# YarnControl_Driver_v1_1.net
KiCad netlist of a schematic drawn in Altium Designer
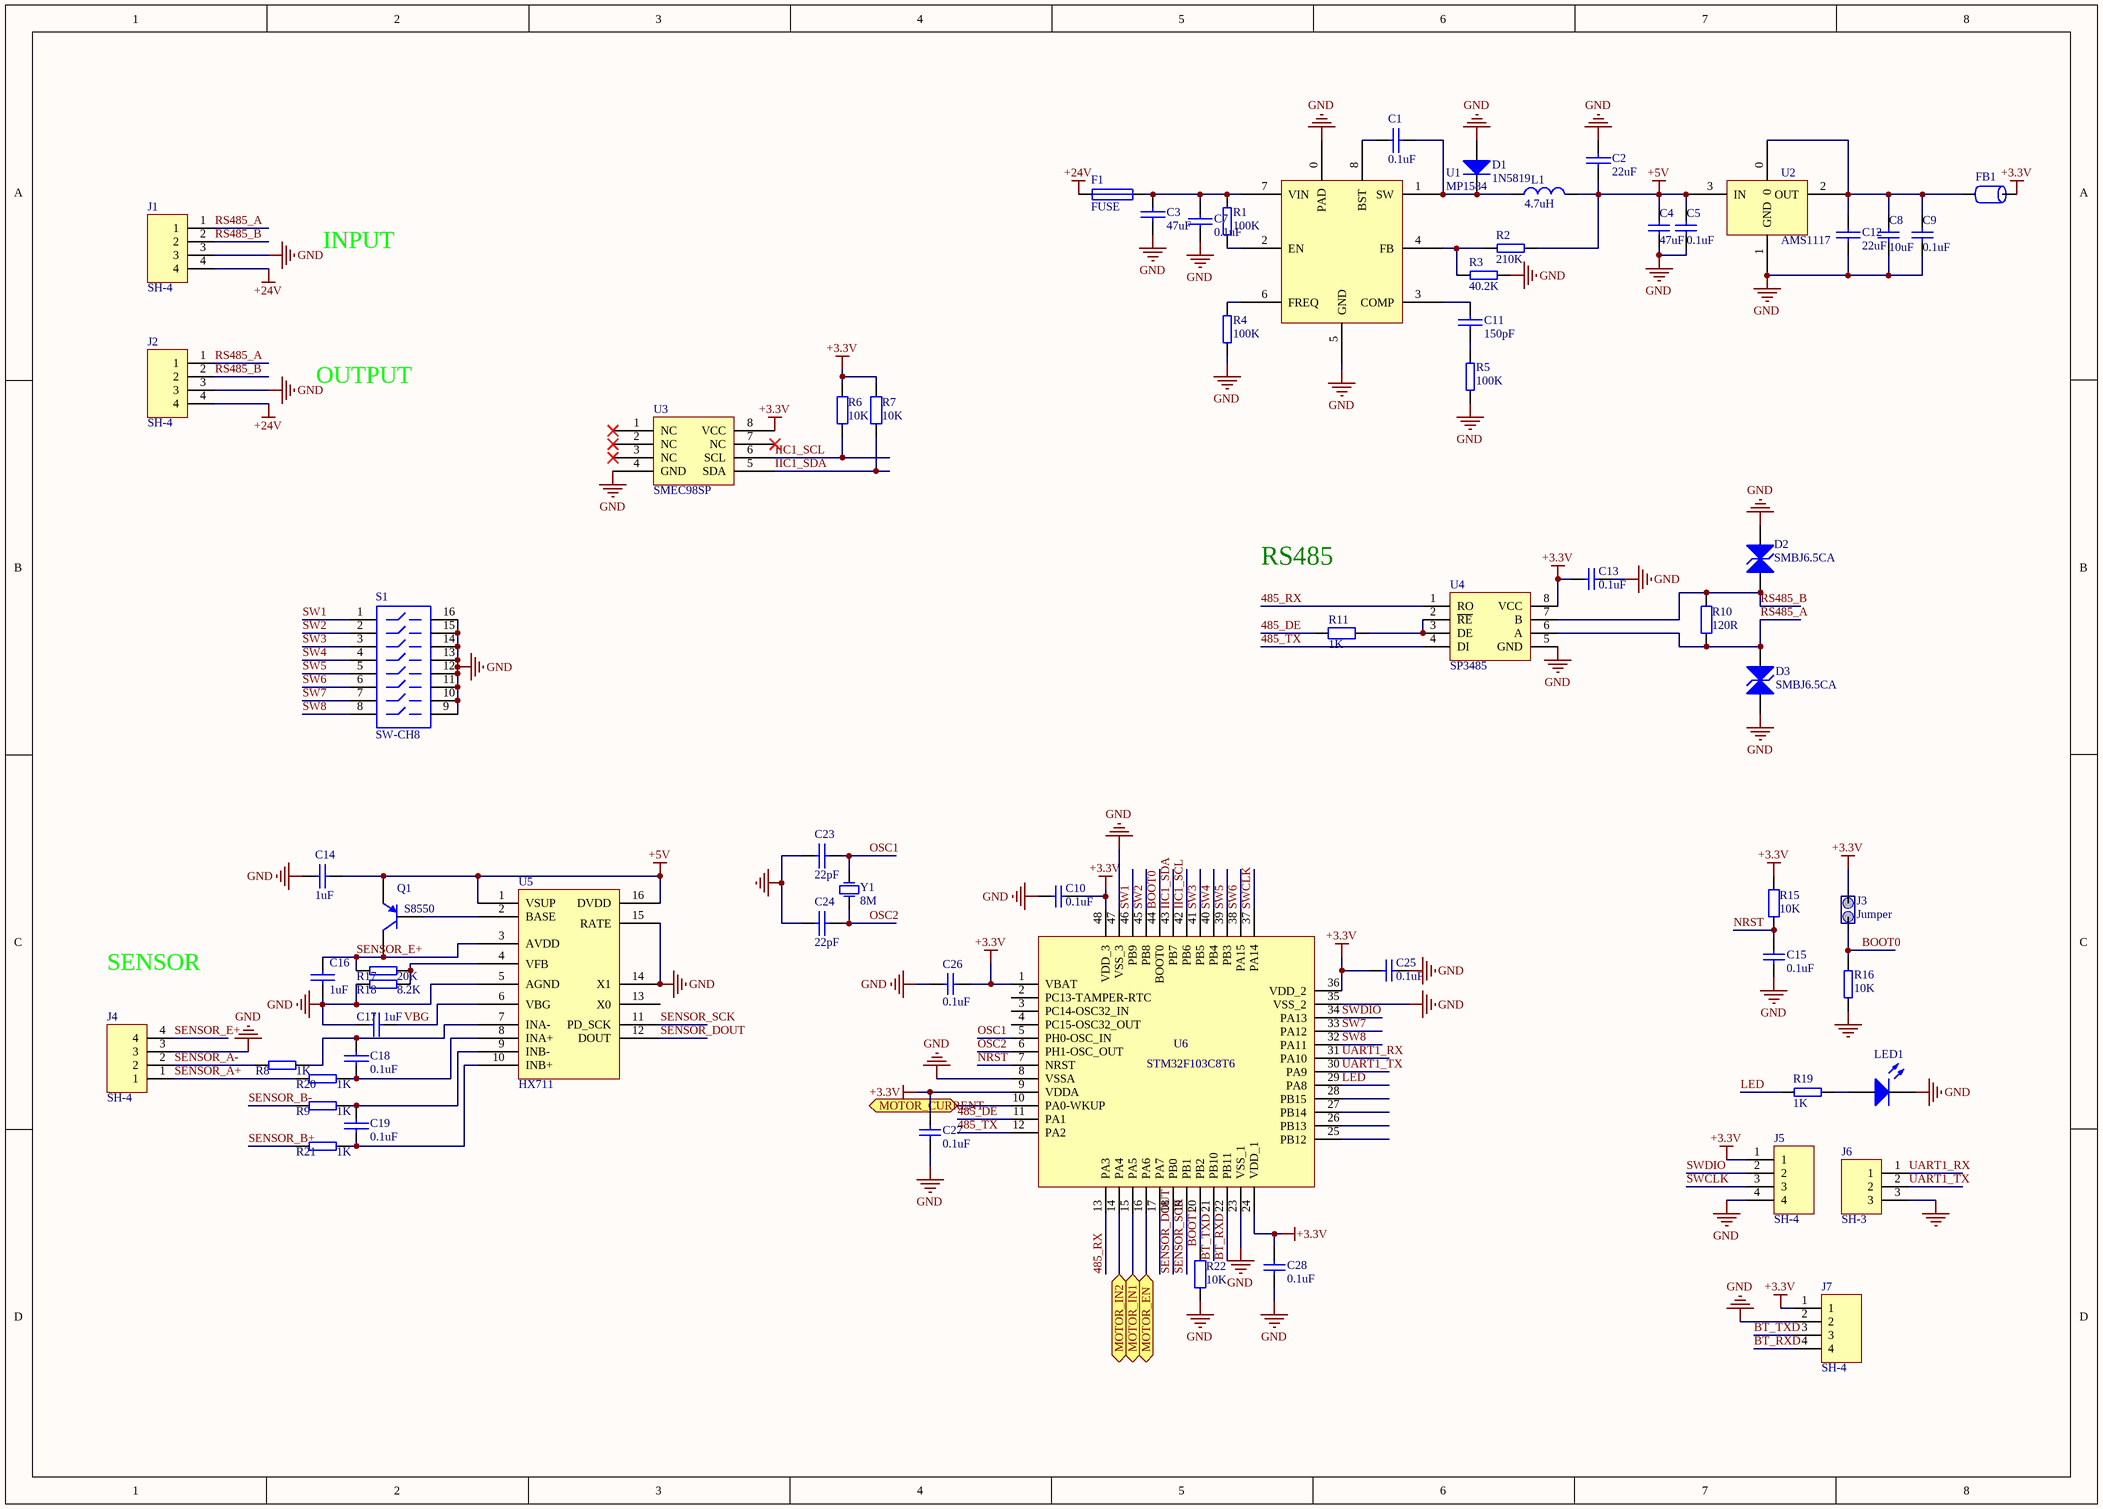
[diagram p0: YarnControl_Driver_v1.1.SchDoc]

(export (version "E")
  (design (tool "Eeschema 10.0.6"))
  (components
    (comp (ref "C1")
      (value "0.1uF")
      (footprint "0805")
      (description "电容")
      (libsource (lib "Component") (part "CAP"))
    )
    (comp (ref "C2")
      (value "22uF")
      (footprint "1206")
      (description "电容")
      (libsource (lib "Component") (part "CAP"))
    )
    (comp (ref "C3")
      (value "47uF")
      (footprint "1812")
      (description "电容")
      (libsource (lib "Component") (part "CAP"))
    )
    (comp (ref "C4") (value "47uF") (footprint "1210") (libsource (lib "Componet") (part "Cap0805")))
    (comp (ref "C5") (value "0.1uF") (footprint "0805") (libsource (lib "Componet") (part "Cap0805")))
    (comp (ref "C7")
      (value "0.1uF")
      (footprint "0805")
      (description "电容")
      (libsource (lib "Component") (part "CAP"))
    )
    (comp (ref "C8") (value "10uF") (footprint "0805") (libsource (lib "Componet") (part "Cap0805")))
    (comp (ref "C9") (value "0.1uF") (footprint "0805") (libsource (lib "Componet") (part "Cap0805")))
    (comp (ref "C10")
      (value "0.1uF")
      (footprint "0805")
      (description "Capacitor")
      (fields (field (name "PUBLISHER") "Altium Limited"))
      (libsource (lib "TIAN's Schlib") (part "Cap"))
    )
    (comp (ref "C11")
      (value "150pF")
      (footprint "0805")
      (description "电容")
      (libsource (lib "Component") (part "CAP"))
    )
    (comp (ref "C12")
      (value "22uF")
      (footprint "1206")
      (description "电容")
      (libsource (lib "Component") (part "CAP"))
    )
    (comp (ref "C13")
      (value "0.1uF")
      (footprint "0805")
      (description "Capacitor")
      (fields (field (name "PUBLISHER") "Altium Limited"))
      (libsource (lib "TIAN's Schlib") (part "Cap"))
    )
    (comp (ref "C14")
      (value "1uF")
      (footprint "0805")
      (description "电容")
      (libsource (lib "Component") (part "CAP"))
    )
    (comp (ref "C15")
      (value "0.1uF")
      (footprint "0805")
      (description "Capacitor")
      (fields (field (name "PUBLISHER") "Altium Limited"))
      (libsource (lib "TIAN's Schlib") (part "Cap"))
    )
    (comp (ref "C16")
      (value "1uF")
      (footprint "0805")
      (description "电容")
      (libsource (lib "Component") (part "CAP"))
    )
    (comp (ref "C17")
      (value "1uF")
      (footprint "0805")
      (description "电容")
      (libsource (lib "Component") (part "CAP"))
    )
    (comp (ref "C18")
      (value "0.1uF")
      (footprint "0805")
      (description "电容")
      (libsource (lib "Component") (part "CAP"))
    )
    (comp (ref "C19")
      (value "0.1uF")
      (footprint "0805")
      (description "电容")
      (libsource (lib "Component") (part "CAP"))
    )
    (comp (ref "C23")
      (value "22pF")
      (footprint "0805")
      (description "电容")
      (libsource (lib "Component") (part "CAP"))
    )
    (comp (ref "C24")
      (value "22pF")
      (footprint "0805")
      (description "电容")
      (libsource (lib "Component") (part "CAP"))
    )
    (comp (ref "C25")
      (value "0.1uF")
      (footprint "0805")
      (description "Capacitor")
      (fields (field (name "PUBLISHER") "Altium Limited"))
      (libsource (lib "TIAN's Schlib") (part "Cap"))
    )
    (comp (ref "C26")
      (value "0.1uF")
      (footprint "0805")
      (description "Capacitor")
      (fields (field (name "PUBLISHER") "Altium Limited"))
      (libsource (lib "TIAN's Schlib") (part "Cap"))
    )
    (comp (ref "C27")
      (value "0.1uF")
      (footprint "0805")
      (description "Capacitor")
      (fields (field (name "PUBLISHER") "Altium Limited"))
      (libsource (lib "TIAN's Schlib") (part "Cap"))
    )
    (comp (ref "C28")
      (value "0.1uF")
      (footprint "0805")
      (description "Capacitor")
      (fields (field (name "PUBLISHER") "Altium Limited"))
      (libsource (lib "TIAN's Schlib") (part "Cap"))
    )
    (comp (ref "D1")
      (value "1N5819")
      (footprint "Diode_TP2")
      (description "二极管")
      (fields (field (name "PUBLISHER") "Altium Limited"))
      (libsource (lib "Component") (part "Diode"))
    )
    (comp (ref "D2")
      (value "SMBJ6.5CA")
      (footprint "SMBJ_DO-214")
      (fields (field (name "PUBLISHER") "Altium Limited"))
      (libsource (lib "TIAN's Schlib") (part "TVS"))
    )
    (comp (ref "D3")
      (value "SMBJ6.5CA")
      (footprint "SMBJ_DO-214")
      (fields (field (name "PUBLISHER") "Altium Limited"))
      (libsource (lib "TIAN's Schlib") (part "TVS"))
    )
    (comp (ref "F1")
      (value "FUSE")
      (footprint "1206")
      (description "保险丝")
      (libsource (lib "Component") (part "FUSE"))
    )
    (comp (ref "FB1") (value "FERRITE") (footprint "0805") (libsource (lib "Connector") (part "FERRITE")))
    (comp (ref "J1") (value "SH-4") (footprint "J5.08_4(NoEar)") (libsource (lib "") (part "SH-4_1")))
    (comp (ref "J2") (value "SH-4") (footprint "J5.08_4(NoEar)") (libsource (lib "") (part "SH-4_1")))
    (comp (ref "J3") (value "Jumper") (footprint "J254-2") (libsource (lib "Connector") (part "Jumper")))
    (comp (ref "J4") (value "SH-4") (footprint "CH3.96-4P") (libsource (lib "") (part "SH-4_2")))
    (comp (ref "J5") (value "SH-4") (footprint "J254-4") (libsource (lib "Connector") (part "SH-4")))
    (comp (ref "J6") (value "SH-3") (footprint "J2.54-3") (libsource (lib "Connector") (part "SH-3")))
    (comp (ref "J7") (value "SH-4") (footprint "J254-4") (libsource (lib "Connector") (part "SH-4")))
    (comp (ref "L1")
      (value "4.7uH")
      (footprint "Inductance6*6")
      (description "电感")
      (libsource (lib "Component") (part "Inductor"))
    )
    (comp (ref "LED1")
      (value "GREEN")
      (footprint "LED")
      (description "Typical RED, GREEN, YELLOW, AMBER GaAs LED")
      (fields (field (name "PUBLISHER") "Altium Limited"))
      (libsource (lib "Miscellaneous Devices") (part "LED2"))
    )
    (comp (ref "Q1") (value "S8550") (footprint "901X_SOT-23") (libsource (lib "Componet") (part "PNP")))
    (comp (ref "R1")
      (value "100K")
      (footprint "0805")
      (description "电阻")
      (libsource (lib "Component") (part "RES"))
    )
    (comp (ref "R2")
      (value "210K")
      (footprint "0805")
      (description "电阻")
      (libsource (lib "Component") (part "RES"))
    )
    (comp (ref "R3")
      (value "40.2K")
      (footprint "0805")
      (description "电阻")
      (libsource (lib "Component") (part "RES"))
    )
    (comp (ref "R4")
      (value "100K")
      (footprint "0805")
      (description "电阻")
      (libsource (lib "Component") (part "RES"))
    )
    (comp (ref "R5")
      (value "100K")
      (footprint "0805")
      (description "电阻")
      (libsource (lib "Component") (part "RES"))
    )
    (comp (ref "R6")
      (value "10K")
      (footprint "0805")
      (description "Resistor")
      (fields (field (name "PUBLISHER") "Altium Limited"))
      (libsource (lib "TIAN's Schlib") (part "Res2"))
    )
    (comp (ref "R7")
      (value "10K")
      (footprint "0805")
      (description "Resistor")
      (fields (field (name "PUBLISHER") "Altium Limited"))
      (libsource (lib "TIAN's Schlib") (part "Res2"))
    )
    (comp (ref "R8")
      (value "1K")
      (footprint "0805")
      (description "电阻")
      (libsource (lib "Component") (part "RES"))
    )
    (comp (ref "R9")
      (value "1K")
      (footprint "0805")
      (description "电阻")
      (libsource (lib "Component") (part "RES"))
    )
    (comp (ref "R10")
      (value "120R")
      (footprint "0805")
      (description "Resistor")
      (fields (field (name "PUBLISHER") "Altium Limited"))
      (libsource (lib "") (part "Res2_1"))
    )
    (comp (ref "R11")
      (value "1K")
      (footprint "0805")
      (description "Resistor")
      (fields (field (name "PUBLISHER") "Altium Limited"))
      (libsource (lib "") (part "Res2_2"))
    )
    (comp (ref "R15")
      (value "10K")
      (footprint "0805")
      (description "Resistor")
      (fields (field (name "PUBLISHER") "Altium Limited"))
      (libsource (lib "TIAN's Schlib") (part "Res2"))
    )
    (comp (ref "R16")
      (value "10K")
      (footprint "0805")
      (description "电阻")
      (libsource (lib "Component") (part "RES"))
    )
    (comp (ref "R17")
      (value "20K")
      (footprint "0805")
      (description "电阻")
      (libsource (lib "Component") (part "RES"))
    )
    (comp (ref "R18")
      (value "8.2K")
      (footprint "0805")
      (description "电阻")
      (libsource (lib "Component") (part "RES"))
    )
    (comp (ref "R19")
      (value "1K")
      (footprint "0805")
      (description "电阻")
      (libsource (lib "Component") (part "RES"))
    )
    (comp (ref "R20")
      (value "1K")
      (footprint "0805")
      (description "电阻")
      (libsource (lib "Component") (part "RES"))
    )
    (comp (ref "R21")
      (value "1K")
      (footprint "0805")
      (description "电阻")
      (libsource (lib "Component") (part "RES"))
    )
    (comp (ref "R22")
      (value "10K")
      (footprint "0805")
      (description "Resistor")
      (fields (field (name "PUBLISHER") "Altium Limited"))
      (libsource (lib "TIAN's Schlib") (part "Res2"))
    )
    (comp (ref "S1")
      (value "SW-CH8")
      (footprint "SWITCH_8")
      (description "拨码开关CH8")
      (fields (field (name "PUBLISHER") "Altium Limited"))
      (libsource (lib "Component") (part "SW-CH8"))
    )
    (comp (ref "U1") (value "MP1584") (footprint "MP1584") (libsource (lib "Chip") (part "MP1584")))
    (comp (ref "U2") (value "AMS1117") (footprint "TO-223") (libsource (lib "Chip") (part "AMS1117")))
    (comp (ref "U3") (value "SMEC98SP") (footprint "SO-8") (libsource (lib "Chip") (part "SMEC98SP")))
    (comp (ref "U4")
      (value "SP3485")
      (footprint "SO-8")
      (description "485")
      (libsource (lib "TIAN's Schlib") (part "SP3485"))
    )
    (comp (ref "U5") (value "HX711") (footprint "SO-16") (libsource (lib "Chip") (part "HX711")))
    (comp (ref "U6")
      (value "STM32F103C8T6")
      (footprint "LQFP_48")
      (libsource (lib "Chip") (part "STM32F103C8T6"))
    )
    (comp (ref "Y1")
      (value "8M")
      (footprint "XTAL")
      (description "Crystal Oscillator")
      (fields (field (name "PUBLISHER") "Altium Limited"))
      (libsource (lib "MY Schlib") (part "XTAL"))
    )
  )
  (nets
    (net (code "1") (name "+3.3V") (class "Default")
      (node (ref "C10") (pin "1") (pinfunction "1_1") (pintype "passive"))
      (node (ref "C13") (pin "2") (pinfunction "2_2") (pintype "passive"))
      (node (ref "C25") (pin "2") (pinfunction "2_2") (pintype "passive"))
      (node (ref "C26") (pin "2") (pinfunction "2_2") (pintype "passive"))
      (node (ref "C27") (pin "2") (pinfunction "2_2") (pintype "passive"))
      (node (ref "C28") (pin "2") (pinfunction "2_2") (pintype "passive"))
      (node (ref "FB1") (pin "2") (pinfunction "2_2") (pintype "passive"))
      (node (ref "J3") (pin "2") (pinfunction "2_2") (pintype "passive"))
      (node (ref "J5") (pin "1") (pinfunction "1_1") (pintype "passive"))
      (node (ref "J7") (pin "1") (pinfunction "1_1") (pintype "passive"))
      (node (ref "R15") (pin "2") (pinfunction "2_2") (pintype "passive"))
      (node (ref "R6") (pin "2") (pinfunction "2_2") (pintype "passive"))
      (node (ref "R7") (pin "2") (pinfunction "2_2") (pintype "passive"))
      (node (ref "U3") (pin "8") (pinfunction "VCC_8") (pintype "passive"))
      (node (ref "U4") (pin "8") (pinfunction "VCC_8") (pintype "passive"))
      (node (ref "U6") (pin "1") (pinfunction "VBAT_1") (pintype "passive"))
      (node (ref "U6") (pin "24") (pinfunction "VDD_1_24") (pintype "passive"))
      (node (ref "U6") (pin "36") (pinfunction "VDD_2_36") (pintype "passive"))
      (node (ref "U6") (pin "48") (pinfunction "VDD_3_48") (pintype "passive"))
      (node (ref "U6") (pin "9") (pinfunction "VDDA_9") (pintype "passive"))
    )
    (net (code "2") (name "+5V") (class "Default")
      (node (ref "C14") (pin "2") (pinfunction "2_2") (pintype "passive"))
      (node (ref "C2") (pin "2") (pinfunction "2_2") (pintype "passive"))
      (node (ref "C4") (pin "2") (pinfunction "2_2") (pintype "passive"))
      (node (ref "C5") (pin "2") (pinfunction "2_2") (pintype "passive"))
      (node (ref "L1") (pin "2") (pinfunction "2_2") (pintype "passive"))
      (node (ref "Q1") (pin "3") (pinfunction "E_3") (pintype "passive"))
      (node (ref "R2") (pin "1") (pinfunction "1_1") (pintype "passive"))
      (node (ref "U2") (pin "3") (pinfunction "IN_3") (pintype "passive"))
      (node (ref "U5") (pin "1") (pinfunction "VSUP_1") (pintype "passive"))
      (node (ref "U5") (pin "16") (pinfunction "DVDD_16") (pintype "passive"))
    )
    (net (code "3") (name "+24V") (class "Default")
      (node (ref "F1") (pin "1") (pinfunction "1_1") (pintype "passive"))
      (node (ref "J1") (pin "4") (pinfunction "4_4") (pintype "passive"))
      (node (ref "J2") (pin "4") (pinfunction "4_4") (pintype "passive"))
    )
    (net (code "4") (name "/485_DE") (class "Default")
      (node (ref "R11") (pin "2") (pinfunction "2_2") (pintype "passive"))
      (node (ref "U6") (pin "11") (pinfunction "PA1_11") (pintype "passive"))
    )
    (net (code "5") (name "/485_RX") (class "Default")
      (node (ref "U4") (pin "1") (pinfunction "RO_1") (pintype "passive"))
      (node (ref "U6") (pin "13") (pinfunction "PA3_13") (pintype "passive"))
    )
    (net (code "6") (name "/485_TX") (class "Default")
      (node (ref "U4") (pin "4") (pinfunction "DI_4") (pintype "passive"))
      (node (ref "U6") (pin "12") (pinfunction "PA2_12") (pintype "passive"))
    )
    (net (code "7") (name "/BOOT0") (class "Default")
      (node (ref "J3") (pin "1") (pinfunction "1_1") (pintype "passive"))
      (node (ref "R16") (pin "1") (pinfunction "1_1") (pintype "passive"))
      (node (ref "U6") (pin "44") (pinfunction "BOOT0_44") (pintype "passive"))
    )
    (net (code "8") (name "/BOOT1") (class "Default")
      (node (ref "R22") (pin "2") (pinfunction "2_2") (pintype "passive"))
      (node (ref "U6") (pin "20") (pinfunction "PB2_20") (pintype "passive"))
    )
    (net (code "9") (name "/BT_RXD") (class "Default")
      (node (ref "J7") (pin "4") (pinfunction "4_4") (pintype "passive"))
      (node (ref "U6") (pin "22") (pinfunction "PB11_22") (pintype "passive"))
    )
    (net (code "10") (name "/BT_TXD") (class "Default")
      (node (ref "J7") (pin "3") (pinfunction "3_3") (pintype "passive"))
      (node (ref "U6") (pin "21") (pinfunction "PB10_21") (pintype "passive"))
    )
    (net (code "11") (name "/IIC1_SCL") (class "Default")
      (node (ref "R6") (pin "1") (pinfunction "1_1") (pintype "passive"))
      (node (ref "U3") (pin "6") (pinfunction "SCL_6") (pintype "passive"))
      (node (ref "U6") (pin "42") (pinfunction "PB6_42") (pintype "passive"))
    )
    (net (code "12") (name "/IIC1_SDA") (class "Default")
      (node (ref "R7") (pin "1") (pinfunction "1_1") (pintype "passive"))
      (node (ref "U3") (pin "5") (pinfunction "SDA_5") (pintype "passive"))
      (node (ref "U6") (pin "43") (pinfunction "PB7_43") (pintype "passive"))
    )
    (net (code "13") (name "/LED") (class "Default")
      (node (ref "R19") (pin "2") (pinfunction "2_2") (pintype "passive"))
      (node (ref "U6") (pin "29") (pinfunction "PA8_29") (pintype "passive"))
    )
    (net (code "14") (name "/MOTOR_CURRENT") (class "Default")
      (node (ref "U6") (pin "10") (pinfunction "PA0-WKUP_10") (pintype "passive"))
    )
    (net (code "15") (name "/MOTOR_EN") (class "Default")
      (node (ref "U6") (pin "16") (pinfunction "PA6_16") (pintype "passive"))
    )
    (net (code "16") (name "/MOTOR_IN1") (class "Default")
      (node (ref "U6") (pin "15") (pinfunction "PA5_15") (pintype "passive"))
    )
    (net (code "17") (name "/MOTOR_IN2") (class "Default")
      (node (ref "U6") (pin "14") (pinfunction "PA4_14") (pintype "passive"))
    )
    (net (code "18") (name "/NRST") (class "Default")
      (node (ref "C15") (pin "2") (pinfunction "2_2") (pintype "passive"))
      (node (ref "R15") (pin "1") (pinfunction "1_1") (pintype "passive"))
      (node (ref "U6") (pin "7") (pinfunction "NRST_7") (pintype "passive"))
    )
    (net (code "19") (name "/OSC1") (class "Default")
      (node (ref "C23") (pin "2") (pinfunction "2_2") (pintype "passive"))
      (node (ref "U6") (pin "5") (pinfunction "PH0-OSC_IN_5") (pintype "passive"))
      (node (ref "Y1") (pin "2") (pinfunction "OSC2_2") (pintype "passive"))
    )
    (net (code "20") (name "/OSC2") (class "Default")
      (node (ref "C24") (pin "2") (pinfunction "2_2") (pintype "passive"))
      (node (ref "U6") (pin "6") (pinfunction "PH1-OSC_OUT_6") (pintype "passive"))
      (node (ref "Y1") (pin "1") (pinfunction "OSC1_1") (pintype "passive"))
    )
    (net (code "21") (name "/RS485_A") (class "Default")
      (node (ref "D3") (pin "2") (pinfunction "K_2") (pintype "passive"))
      (node (ref "J1") (pin "1") (pinfunction "1_1") (pintype "passive"))
      (node (ref "J2") (pin "1") (pinfunction "1_1") (pintype "passive"))
      (node (ref "R10") (pin "2") (pinfunction "2_2") (pintype "passive"))
      (node (ref "U4") (pin "6") (pinfunction "A_6") (pintype "passive"))
    )
    (net (code "22") (name "/RS485_B") (class "Default")
      (node (ref "D2") (pin "1") (pinfunction "A_1") (pintype "passive"))
      (node (ref "J1") (pin "2") (pinfunction "2_2") (pintype "passive"))
      (node (ref "J2") (pin "2") (pinfunction "2_2") (pintype "passive"))
      (node (ref "R10") (pin "1") (pinfunction "1_1") (pintype "passive"))
      (node (ref "U4") (pin "7") (pinfunction "B_7") (pintype "passive"))
    )
    (net (code "23") (name "/SENSOR_A+") (class "Default")
      (node (ref "J4") (pin "1") (pinfunction "1_1") (pintype "passive"))
      (node (ref "R20") (pin "2") (pinfunction "2_2") (pintype "passive"))
    )
    (net (code "24") (name "/SENSOR_A-") (class "Default")
      (node (ref "J4") (pin "2") (pinfunction "2_2") (pintype "passive"))
      (node (ref "R8") (pin "2") (pinfunction "2_2") (pintype "passive"))
    )
    (net (code "25") (name "/SENSOR_B+") (class "Default")
      (node (ref "R21") (pin "2") (pinfunction "2_2") (pintype "passive"))
    )
    (net (code "26") (name "/SENSOR_B-") (class "Default")
      (node (ref "R9") (pin "2") (pinfunction "2_2") (pintype "passive"))
    )
    (net (code "27") (name "/SENSOR_DOUT") (class "Default")
      (node (ref "U5") (pin "12") (pinfunction "DOUT_12") (pintype "passive"))
      (node (ref "U6") (pin "18") (pinfunction "PB0_18") (pintype "passive"))
    )
    (net (code "28") (name "/SENSOR_E+") (class "Default")
      (node (ref "C16") (pin "2") (pinfunction "2_2") (pintype "passive"))
      (node (ref "J4") (pin "4") (pinfunction "4_4") (pintype "passive"))
      (node (ref "Q1") (pin "1") (pinfunction "C_1") (pintype "passive"))
      (node (ref "R17") (pin "2") (pinfunction "2_2") (pintype "passive"))
      (node (ref "U5") (pin "3") (pinfunction "AVDD_3") (pintype "passive"))
    )
    (net (code "29") (name "/SENSOR_SCK") (class "Default")
      (node (ref "U5") (pin "11") (pinfunction "PD_SCK_11") (pintype "passive"))
      (node (ref "U6") (pin "19") (pinfunction "PB1_19") (pintype "passive"))
    )
    (net (code "30") (name "/SW1") (class "Default")
      (node (ref "S1") (pin "1") (pinfunction "1_1") (pintype "passive"))
      (node (ref "U6") (pin "46") (pinfunction "PB9_46") (pintype "passive"))
    )
    (net (code "31") (name "/SW2") (class "Default")
      (node (ref "S1") (pin "2") (pinfunction "2_2") (pintype "passive"))
      (node (ref "U6") (pin "45") (pinfunction "PB8_45") (pintype "passive"))
    )
    (net (code "32") (name "/SW3") (class "Default")
      (node (ref "S1") (pin "3") (pinfunction "3_3") (pintype "passive"))
      (node (ref "U6") (pin "41") (pinfunction "PB5_41") (pintype "passive"))
    )
    (net (code "33") (name "/SW4") (class "Default")
      (node (ref "S1") (pin "4") (pinfunction "4_4") (pintype "passive"))
      (node (ref "U6") (pin "40") (pinfunction "PB4_40") (pintype "passive"))
    )
    (net (code "34") (name "/SW5") (class "Default")
      (node (ref "S1") (pin "5") (pinfunction "5_5") (pintype "passive"))
      (node (ref "U6") (pin "39") (pinfunction "PB3_39") (pintype "passive"))
    )
    (net (code "35") (name "/SW6") (class "Default")
      (node (ref "S1") (pin "6") (pinfunction "6_6") (pintype "passive"))
      (node (ref "U6") (pin "38") (pinfunction "PA15_38") (pintype "passive"))
    )
    (net (code "36") (name "/SW7") (class "Default")
      (node (ref "S1") (pin "7") (pinfunction "7_7") (pintype "passive"))
      (node (ref "U6") (pin "33") (pinfunction "PA12_33") (pintype "passive"))
    )
    (net (code "37") (name "/SW8") (class "Default")
      (node (ref "S1") (pin "8") (pinfunction "8_8") (pintype "passive"))
      (node (ref "U6") (pin "32") (pinfunction "PA11_32") (pintype "passive"))
    )
    (net (code "38") (name "/SWCLK") (class "Default")
      (node (ref "J5") (pin "3") (pinfunction "3_3") (pintype "passive"))
      (node (ref "U6") (pin "37") (pinfunction "PA14_37") (pintype "passive"))
    )
    (net (code "39") (name "/SWDIO") (class "Default")
      (node (ref "J5") (pin "2") (pinfunction "2_2") (pintype "passive"))
      (node (ref "U6") (pin "34") (pinfunction "PA13_34") (pintype "passive"))
    )
    (net (code "40") (name "/UART1_RX") (class "Default")
      (node (ref "J6") (pin "1") (pinfunction "1_1") (pintype "passive"))
      (node (ref "U6") (pin "31") (pinfunction "PA10_31") (pintype "passive"))
    )
    (net (code "41") (name "/UART1_TX") (class "Default")
      (node (ref "J6") (pin "2") (pinfunction "2_2") (pintype "passive"))
      (node (ref "U6") (pin "30") (pinfunction "PA9_30") (pintype "passive"))
    )
    (net (code "42") (name "/VBG") (class "Default")
      (node (ref "C17") (pin "1") (pinfunction "1_1") (pintype "passive"))
      (node (ref "U5") (pin "6") (pinfunction "VBG_6") (pintype "passive"))
    )
    (net (code "43") (name "GND") (class "Default")
      (node (ref "C10") (pin "2") (pinfunction "2_2") (pintype "passive"))
      (node (ref "C12") (pin "2") (pinfunction "2_2") (pintype "passive"))
      (node (ref "C13") (pin "1") (pinfunction "1_1") (pintype "passive"))
      (node (ref "C14") (pin "1") (pinfunction "1_1") (pintype "passive"))
      (node (ref "C15") (pin "1") (pinfunction "1_1") (pintype "passive"))
      (node (ref "C16") (pin "1") (pinfunction "1_1") (pintype "passive"))
      (node (ref "C17") (pin "2") (pinfunction "2_2") (pintype "passive"))
      (node (ref "C2") (pin "1") (pinfunction "1_1") (pintype "passive"))
      (node (ref "C23") (pin "1") (pinfunction "1_1") (pintype "passive"))
      (node (ref "C24") (pin "1") (pinfunction "1_1") (pintype "passive"))
      (node (ref "C25") (pin "1") (pinfunction "1_1") (pintype "passive"))
      (node (ref "C26") (pin "1") (pinfunction "1_1") (pintype "passive"))
      (node (ref "C27") (pin "1") (pinfunction "1_1") (pintype "passive"))
      (node (ref "C28") (pin "1") (pinfunction "1_1") (pintype "passive"))
      (node (ref "C3") (pin "2") (pinfunction "2_2") (pintype "passive"))
      (node (ref "C4") (pin "1") (pinfunction "1_1") (pintype "passive"))
      (node (ref "C5") (pin "1") (pinfunction "1_1") (pintype "passive"))
      (node (ref "C7") (pin "2") (pinfunction "2_2") (pintype "passive"))
      (node (ref "C8") (pin "1") (pinfunction "1_1") (pintype "passive"))
      (node (ref "C9") (pin "1") (pinfunction "1_1") (pintype "passive"))
      (node (ref "D1") (pin "1") (pinfunction "A_1") (pintype "passive"))
      (node (ref "D2") (pin "2") (pinfunction "K_2") (pintype "passive"))
      (node (ref "D3") (pin "1") (pinfunction "A_1") (pintype "passive"))
      (node (ref "J1") (pin "3") (pinfunction "3_3") (pintype "passive"))
      (node (ref "J2") (pin "3") (pinfunction "3_3") (pintype "passive"))
      (node (ref "J4") (pin "3") (pinfunction "3_3") (pintype "passive"))
      (node (ref "J5") (pin "4") (pinfunction "4_4") (pintype "passive"))
      (node (ref "J6") (pin "3") (pinfunction "3_3") (pintype "passive"))
      (node (ref "J7") (pin "2") (pinfunction "2_2") (pintype "passive"))
      (node (ref "LED1") (pin "2") (pinfunction "K_2") (pintype "passive"))
      (node (ref "R16") (pin "2") (pinfunction "2_2") (pintype "passive"))
      (node (ref "R18") (pin "2") (pinfunction "2_2") (pintype "passive"))
      (node (ref "R22") (pin "1") (pinfunction "1_1") (pintype "passive"))
      (node (ref "R3") (pin "1") (pinfunction "1_1") (pintype "passive"))
      (node (ref "R4") (pin "1") (pinfunction "1_1") (pintype "passive"))
      (node (ref "R5") (pin "1") (pinfunction "1_1") (pintype "passive"))
      (node (ref "S1") (pin "10") (pinfunction "10_10") (pintype "passive"))
      (node (ref "S1") (pin "11") (pinfunction "11_11") (pintype "passive"))
      (node (ref "S1") (pin "12") (pinfunction "12_12") (pintype "passive"))
      (node (ref "S1") (pin "13") (pinfunction "13_13") (pintype "passive"))
      (node (ref "S1") (pin "14") (pinfunction "14_14") (pintype "passive"))
      (node (ref "S1") (pin "15") (pinfunction "15_15") (pintype "passive"))
      (node (ref "S1") (pin "16") (pinfunction "16_16") (pintype "passive"))
      (node (ref "S1") (pin "9") (pinfunction "9_9") (pintype "passive"))
      (node (ref "U1") (pin "0") (pinfunction "PAD_0") (pintype "passive"))
      (node (ref "U1") (pin "5") (pinfunction "GND_5") (pintype "passive"))
      (node (ref "U2") (pin "1") (pinfunction "GND_1") (pintype "passive"))
      (node (ref "U3") (pin "4") (pinfunction "GND_4") (pintype "passive"))
      (node (ref "U4") (pin "5") (pinfunction "GND_5") (pintype "passive"))
      (node (ref "U5") (pin "14") (pinfunction "X1_14") (pintype "passive"))
      (node (ref "U5") (pin "15") (pinfunction "RATE_15") (pintype "passive"))
      (node (ref "U5") (pin "5") (pinfunction "AGND_5") (pintype "passive"))
      (node (ref "U6") (pin "23") (pinfunction "VSS_1_23") (pintype "passive"))
      (node (ref "U6") (pin "35") (pinfunction "VSS_2_35") (pintype "passive"))
      (node (ref "U6") (pin "47") (pinfunction "VSS_3_47") (pintype "passive"))
      (node (ref "U6") (pin "8") (pinfunction "VSSA_8") (pintype "passive"))
    )
    (net (code "44") (name "Net-(C11-Pad2)") (class "Default")
      (node (ref "C11") (pin "2") (pinfunction "2_2") (pintype "passive"))
      (node (ref "R5") (pin "2") (pinfunction "2_2") (pintype "passive"))
    )
    (net (code "45") (name "Net-(D1-K)") (class "Default")
      (node (ref "C1") (pin "2") (pinfunction "2_2") (pintype "passive"))
      (node (ref "D1") (pin "2") (pinfunction "K_2") (pintype "passive"))
      (node (ref "L1") (pin "1") (pinfunction "1_1") (pintype "passive"))
      (node (ref "U1") (pin "1") (pinfunction "SW_1") (pintype "passive"))
    )
    (net (code "46") (name "Net-(LED1-A)") (class "Default")
      (node (ref "LED1") (pin "1") (pinfunction "A_1") (pintype "passive"))
      (node (ref "R19") (pin "1") (pinfunction "1_1") (pintype "passive"))
    )
    (net (code "47") (name "Net-(Q1-B)") (class "Default")
      (node (ref "Q1") (pin "2") (pinfunction "B_2") (pintype "passive"))
      (node (ref "U5") (pin "2") (pinfunction "BASE_2") (pintype "passive"))
    )
    (net (code "48") (name "Net-(U1-BST)") (class "Default")
      (node (ref "C1") (pin "1") (pinfunction "1_1") (pintype "passive"))
      (node (ref "U1") (pin "8") (pinfunction "BST_8") (pintype "passive"))
    )
    (net (code "49") (name "Net-(U1-COMP)") (class "Default")
      (node (ref "C11") (pin "1") (pinfunction "1_1") (pintype "passive"))
      (node (ref "U1") (pin "3") (pinfunction "COMP_3") (pintype "passive"))
    )
    (net (code "50") (name "Net-(U1-EN)") (class "Default")
      (node (ref "R1") (pin "1") (pinfunction "1_1") (pintype "passive"))
      (node (ref "U1") (pin "2") (pinfunction "EN_2") (pintype "passive"))
    )
    (net (code "51") (name "Net-(U1-FB)") (class "Default")
      (node (ref "R2") (pin "2") (pinfunction "2_2") (pintype "passive"))
      (node (ref "R3") (pin "2") (pinfunction "2_2") (pintype "passive"))
      (node (ref "U1") (pin "4") (pinfunction "FB_4") (pintype "passive"))
    )
    (net (code "52") (name "Net-(U1-FREQ)") (class "Default")
      (node (ref "R4") (pin "2") (pinfunction "2_2") (pintype "passive"))
      (node (ref "U1") (pin "6") (pinfunction "FREQ_6") (pintype "passive"))
    )
    (net (code "53") (name "Net-(U1-VIN)") (class "Default")
      (node (ref "C3") (pin "1") (pinfunction "1_1") (pintype "passive"))
      (node (ref "C7") (pin "1") (pinfunction "1_1") (pintype "passive"))
      (node (ref "F1") (pin "2") (pinfunction "2_2") (pintype "passive"))
      (node (ref "R1") (pin "2") (pinfunction "2_2") (pintype "passive"))
      (node (ref "U1") (pin "7") (pinfunction "VIN_7") (pintype "passive"))
    )
    (net (code "54") (name "Net-(U2-OUT)") (class "Default")
      (node (ref "C12") (pin "1") (pinfunction "1_1") (pintype "passive"))
      (node (ref "C8") (pin "2") (pinfunction "2_2") (pintype "passive"))
      (node (ref "C9") (pin "2") (pinfunction "2_2") (pintype "passive"))
      (node (ref "FB1") (pin "1") (pinfunction "1_1") (pintype "passive"))
      (node (ref "U2") (pin "0") (pinfunction "0_0") (pintype "passive"))
      (node (ref "U2") (pin "2") (pinfunction "OUT_2") (pintype "passive"))
    )
    (net (code "55") (name "Net-(U4-DE)") (class "Default")
      (node (ref "R11") (pin "1") (pinfunction "1_1") (pintype "passive"))
      (node (ref "U4") (pin "2") (pinfunction "~{RE}_2") (pintype "passive"))
      (node (ref "U4") (pin "3") (pinfunction "DE_3") (pintype "passive"))
    )
    (net (code "56") (name "Net-(U5-INA+)") (class "Default")
      (node (ref "C18") (pin "2") (pinfunction "2_2") (pintype "passive"))
      (node (ref "R20") (pin "1") (pinfunction "1_1") (pintype "passive"))
      (node (ref "U5") (pin "8") (pinfunction "INA+_8") (pintype "passive"))
    )
    (net (code "57") (name "Net-(U5-INA-)") (class "Default")
      (node (ref "C18") (pin "1") (pinfunction "1_1") (pintype "passive"))
      (node (ref "R8") (pin "1") (pinfunction "1_1") (pintype "passive"))
      (node (ref "U5") (pin "7") (pinfunction "INA-_7") (pintype "passive"))
    )
    (net (code "58") (name "Net-(U5-INB+)") (class "Default")
      (node (ref "C19") (pin "2") (pinfunction "2_2") (pintype "passive"))
      (node (ref "R21") (pin "1") (pinfunction "1_1") (pintype "passive"))
      (node (ref "U5") (pin "10") (pinfunction "INB+_10") (pintype "passive"))
    )
    (net (code "59") (name "Net-(U5-INB-)") (class "Default")
      (node (ref "C19") (pin "1") (pinfunction "1_1") (pintype "passive"))
      (node (ref "R9") (pin "1") (pinfunction "1_1") (pintype "passive"))
      (node (ref "U5") (pin "9") (pinfunction "INB-_9") (pintype "passive"))
    )
    (net (code "60") (name "Net-(U5-VFB)") (class "Default")
      (node (ref "R17") (pin "1") (pinfunction "1_1") (pintype "passive"))
      (node (ref "R18") (pin "1") (pinfunction "1_1") (pintype "passive"))
      (node (ref "U5") (pin "4") (pinfunction "VFB_4") (pintype "passive"))
    )
    (net (code "61") (name "unconnected-(U3-NC-Pad1)") (class "Default")
      (node (ref "U3") (pin "1") (pinfunction "NC_1") (pintype "passive+no_connect"))
    )
    (net (code "62") (name "unconnected-(U3-NC-Pad2)") (class "Default")
      (node (ref "U3") (pin "2") (pinfunction "NC_2") (pintype "passive+no_connect"))
    )
    (net (code "63") (name "unconnected-(U3-NC-Pad3)") (class "Default")
      (node (ref "U3") (pin "3") (pinfunction "NC_3") (pintype "passive+no_connect"))
    )
    (net (code "64") (name "unconnected-(U3-NC-Pad7)") (class "Default")
      (node (ref "U3") (pin "7") (pinfunction "NC_7") (pintype "passive+no_connect"))
    )
    (net (code "65") (name "unconnected-(U5-X0-Pad13)") (class "Default")
      (node (ref "U5") (pin "13") (pinfunction "X0_13") (pintype "passive"))
    )
    (net (code "66") (name "unconnected-(U6-PA7-Pad17)") (class "Default")
      (node (ref "U6") (pin "17") (pinfunction "PA7_17") (pintype "passive"))
    )
    (net (code "67") (name "unconnected-(U6-PB12-Pad25)") (class "Default")
      (node (ref "U6") (pin "25") (pinfunction "PB12_25") (pintype "passive"))
    )
    (net (code "68") (name "unconnected-(U6-PB13-Pad26)") (class "Default")
      (node (ref "U6") (pin "26") (pinfunction "PB13_26") (pintype "passive"))
    )
    (net (code "69") (name "unconnected-(U6-PB14-Pad27)") (class "Default")
      (node (ref "U6") (pin "27") (pinfunction "PB14_27") (pintype "passive"))
    )
    (net (code "70") (name "unconnected-(U6-PB15-Pad28)") (class "Default")
      (node (ref "U6") (pin "28") (pinfunction "PB15_28") (pintype "passive"))
    )
    (net (code "71") (name "unconnected-(U6-PC13-TAMPER-RTC-Pad2)") (class "Default")
      (node (ref "U6") (pin "2") (pinfunction "PC13-TAMPER-RTC_2") (pintype "passive"))
    )
    (net (code "72") (name "unconnected-(U6-PC14-OSC32_IN-Pad3)") (class "Default")
      (node (ref "U6") (pin "3") (pinfunction "PC14-OSC32_IN_3") (pintype "passive"))
    )
    (net (code "73") (name "unconnected-(U6-PC15-OSC32_OUT-Pad4)") (class "Default")
      (node (ref "U6") (pin "4") (pinfunction "PC15-OSC32_OUT_4") (pintype "passive"))
    )
  )
)
